# SCH_PCB-Card-2026-01-05.net
KiCad netlist of a schematic drawn in EasyEDA
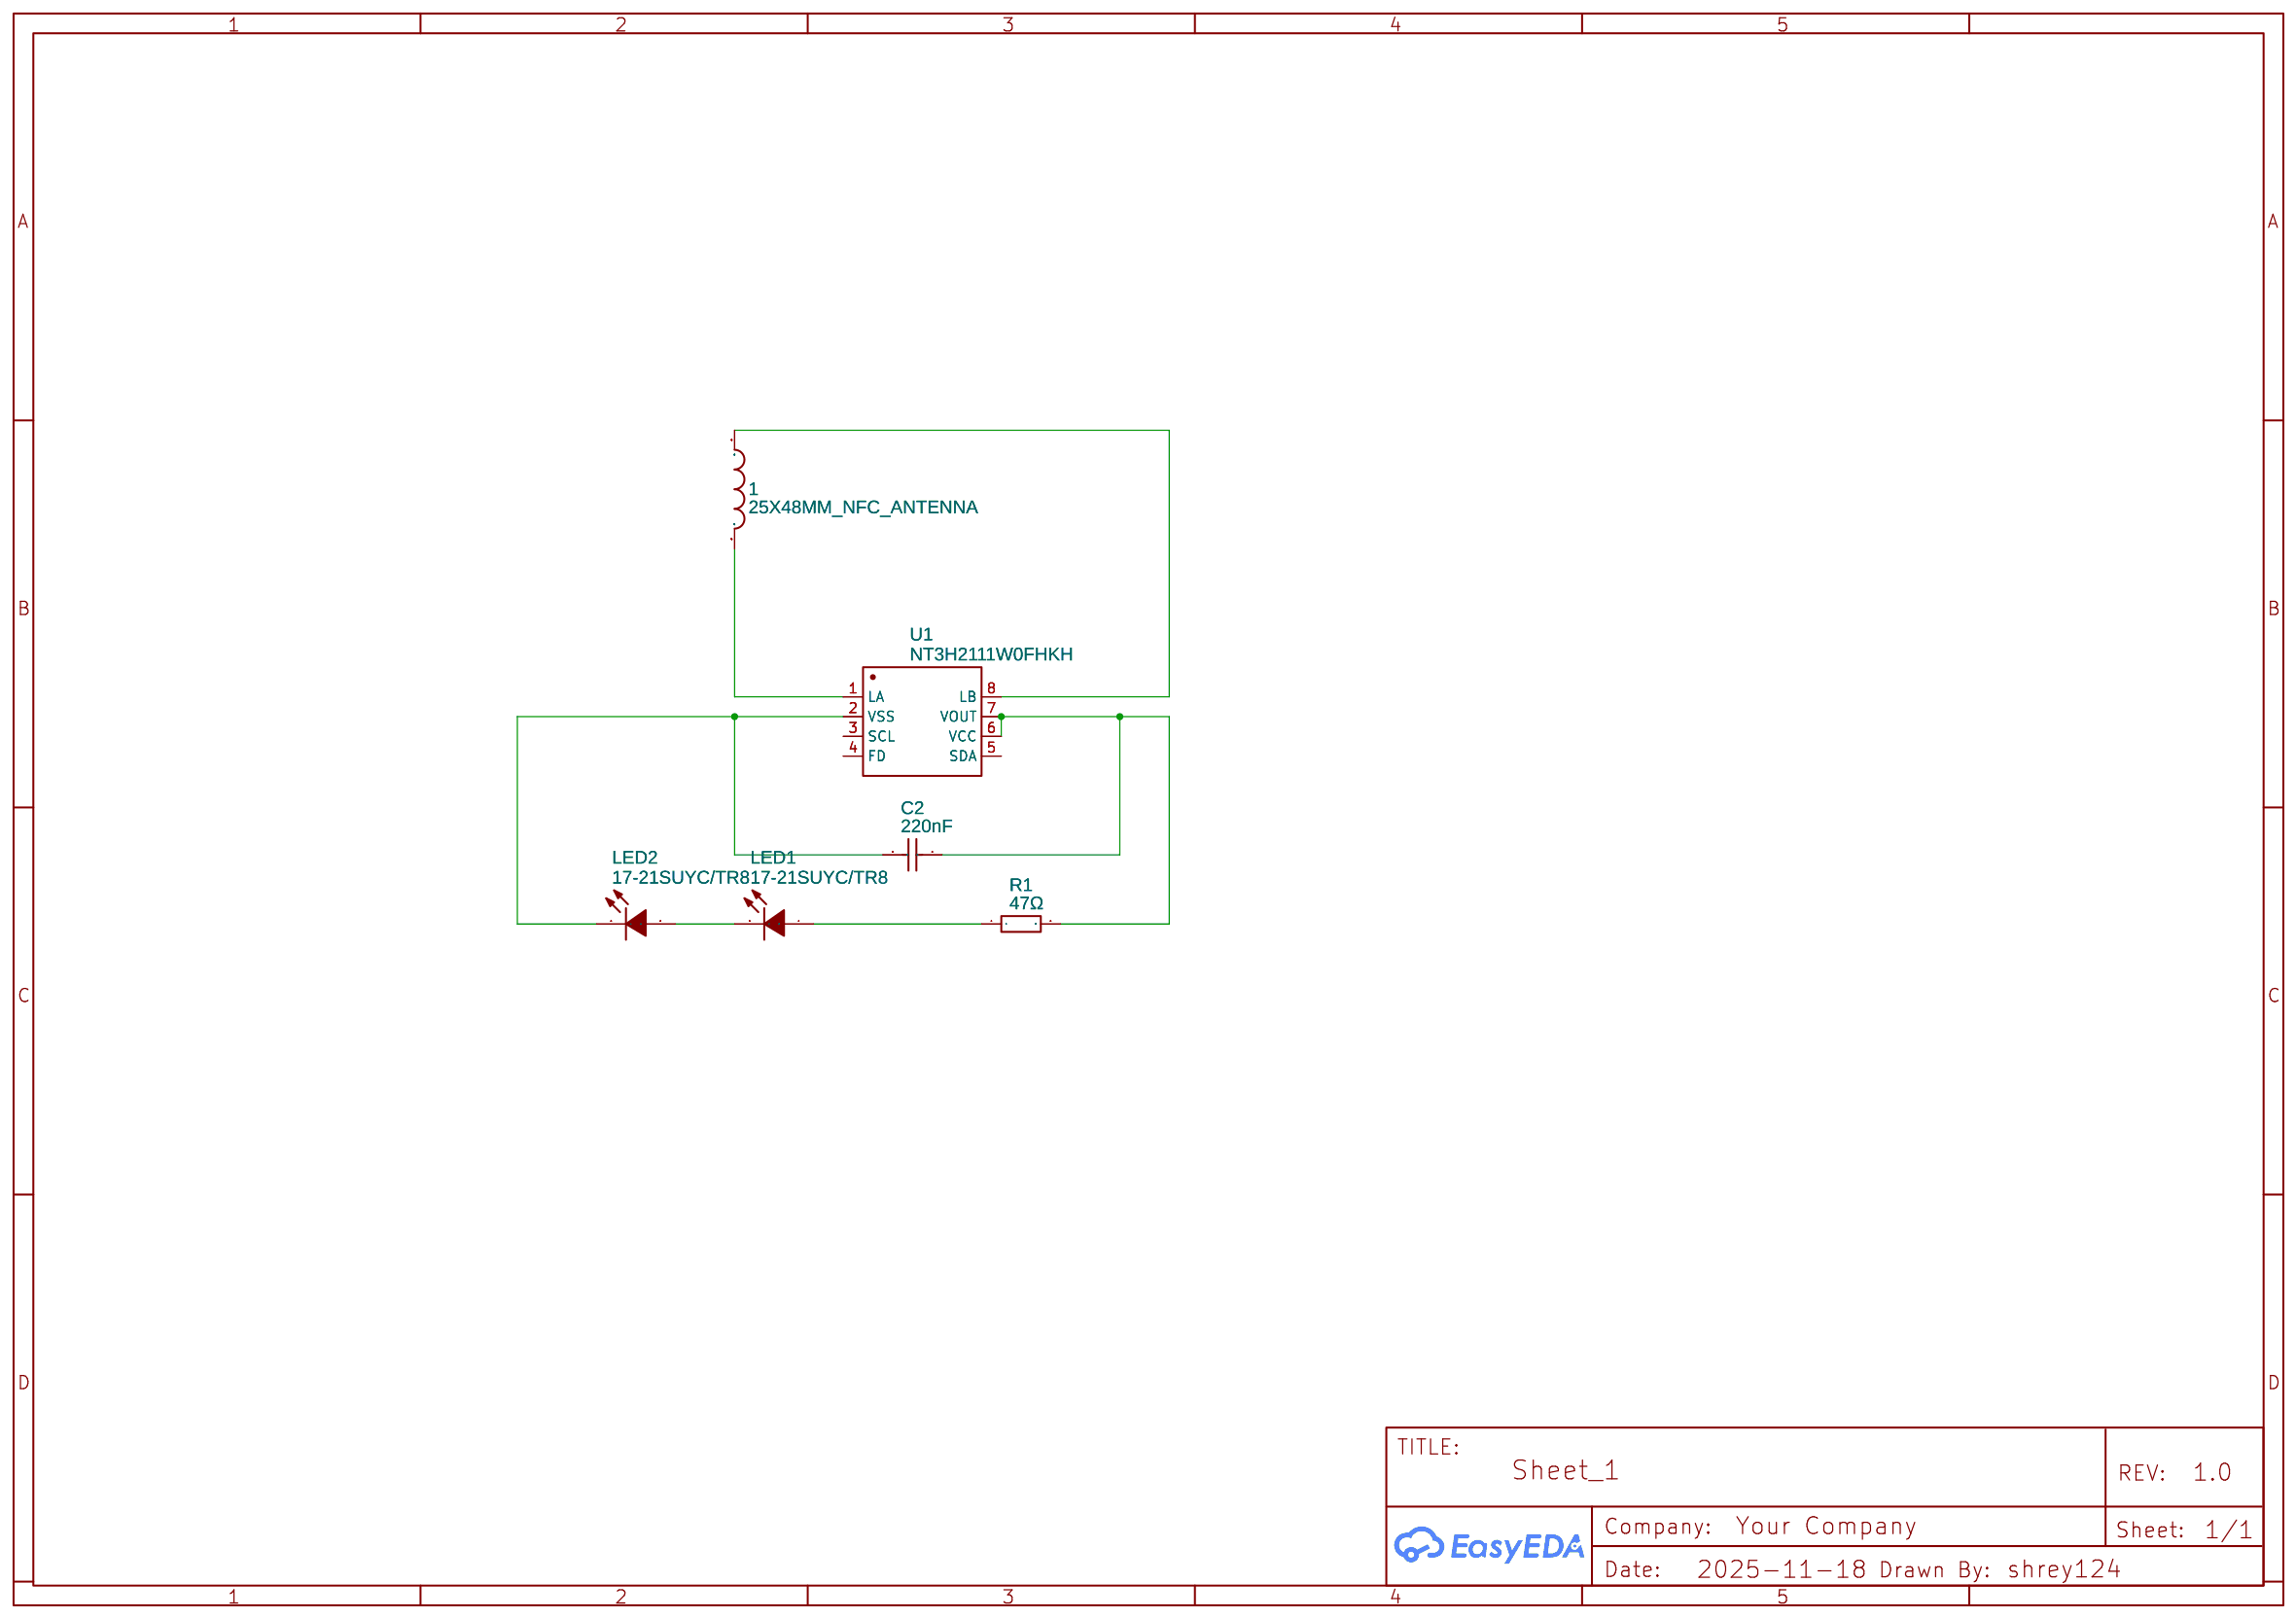
[diagram p0: schematic sheet]

(export (version "E")
  (design (tool "Eeschema 10.0.6"))
  (components
    (comp (ref "1") (value "25X48MM_NFC_ANTENNA") (libsource (lib "") (part "25X48MM_NFC_ANTENNA")))
    (comp (ref "C2")
      (value "220nF")
      (fields
        (field (name "Manufacturer Part") "CL10B224KA8NNNC")
        (field (name "Manufacturer") "SAMSUNG(三星)")
      )
      (libsource (lib "") (part "CL10B224KA8NNNC"))
    )
    (comp (ref "LED1")
      (value "17-21SUYC/TR8")
      (fields (field (name "Manufacturer Part") "KT-0805黄灯") (field (name "Manufacturer") "KENTO"))
      (libsource (lib "") (part "17-21SUYC/TR8"))
    )
    (comp (ref "LED2")
      (value "17-21SUYC/TR8")
      (fields (field (name "Manufacturer Part") "KT-0805黄灯") (field (name "Manufacturer") "KENTO"))
      (libsource (lib "") (part "17-21SUYC/TR8"))
    )
    (comp (ref "R1")
      (value "47Ω")
      (fields
        (field (name "Manufacturer Part") "0603WAF470JT5E")
        (field (name "Manufacturer") "UNI-ROYAL(厚声)")
      )
      (libsource (lib "") (part "0603WAF470JT5E"))
    )
    (comp (ref "U1")
      (value "NT3H2111W0FHKH")
      (fields (field (name "Manufacturer") "NXP(恩智浦)"))
      (libsource (lib "") (part "NT3H2111W0FHKH"))
    )
  )
  (nets
    (net (code "1") (name "Net-(LED1-+)") (class "Default")
      (node (ref "LED1") (pin "1") (pinfunction "+_1") (pintype "unspecified"))
      (node (ref "R1") (pin "1") (pinfunction "1_1") (pintype "input"))
    )
    (net (code "2") (name "Net-(LED1--)") (class "Default")
      (node (ref "LED1") (pin "2") (pinfunction "-_2") (pintype "unspecified"))
      (node (ref "LED2") (pin "1") (pinfunction "+_1") (pintype "unspecified"))
    )
    (net (code "3") (name "Net-(LED2--)") (class "Default")
      (node (ref "C2") (pin "1") (pinfunction "1_1") (pintype "input"))
      (node (ref "LED2") (pin "2") (pinfunction "-_2") (pintype "unspecified"))
      (node (ref "U1") (pin "2") (pinfunction "VSS_2") (pintype "unspecified"))
    )
    (net (code "4") (name "Net-(U1-LA)") (class "Default")
      (node (ref "1") (pin "P$2") (pinfunction "P$2_P$2") (pintype "bidirectional"))
      (node (ref "U1") (pin "1") (pinfunction "LA_1") (pintype "unspecified"))
    )
    (net (code "5") (name "Net-(U1-LB)") (class "Default")
      (node (ref "1") (pin "P$1") (pinfunction "P$1_P$1") (pintype "bidirectional"))
      (node (ref "U1") (pin "8") (pinfunction "LB_8") (pintype "unspecified"))
    )
    (net (code "6") (name "Net-(U1-VCC)") (class "Default")
      (node (ref "C2") (pin "2") (pinfunction "2_2") (pintype "input"))
      (node (ref "R1") (pin "2") (pinfunction "2_2") (pintype "input"))
      (node (ref "U1") (pin "6") (pinfunction "VCC_6") (pintype "unspecified"))
      (node (ref "U1") (pin "7") (pinfunction "VOUT_7") (pintype "unspecified"))
    )
    (net (code "7") (name "unconnected-(U1-FD-Pad4)") (class "Default")
      (node (ref "U1") (pin "4") (pinfunction "FD_4") (pintype "unspecified"))
    )
    (net (code "8") (name "unconnected-(U1-SCL-Pad3)") (class "Default")
      (node (ref "U1") (pin "3") (pinfunction "SCL_3") (pintype "unspecified"))
    )
    (net (code "9") (name "unconnected-(U1-SDA-Pad5)") (class "Default")
      (node (ref "U1") (pin "5") (pinfunction "SDA_5") (pintype "unspecified"))
    )
  )
)
